# Prototype2.net
KiCad netlist of a schematic drawn in EAGLE
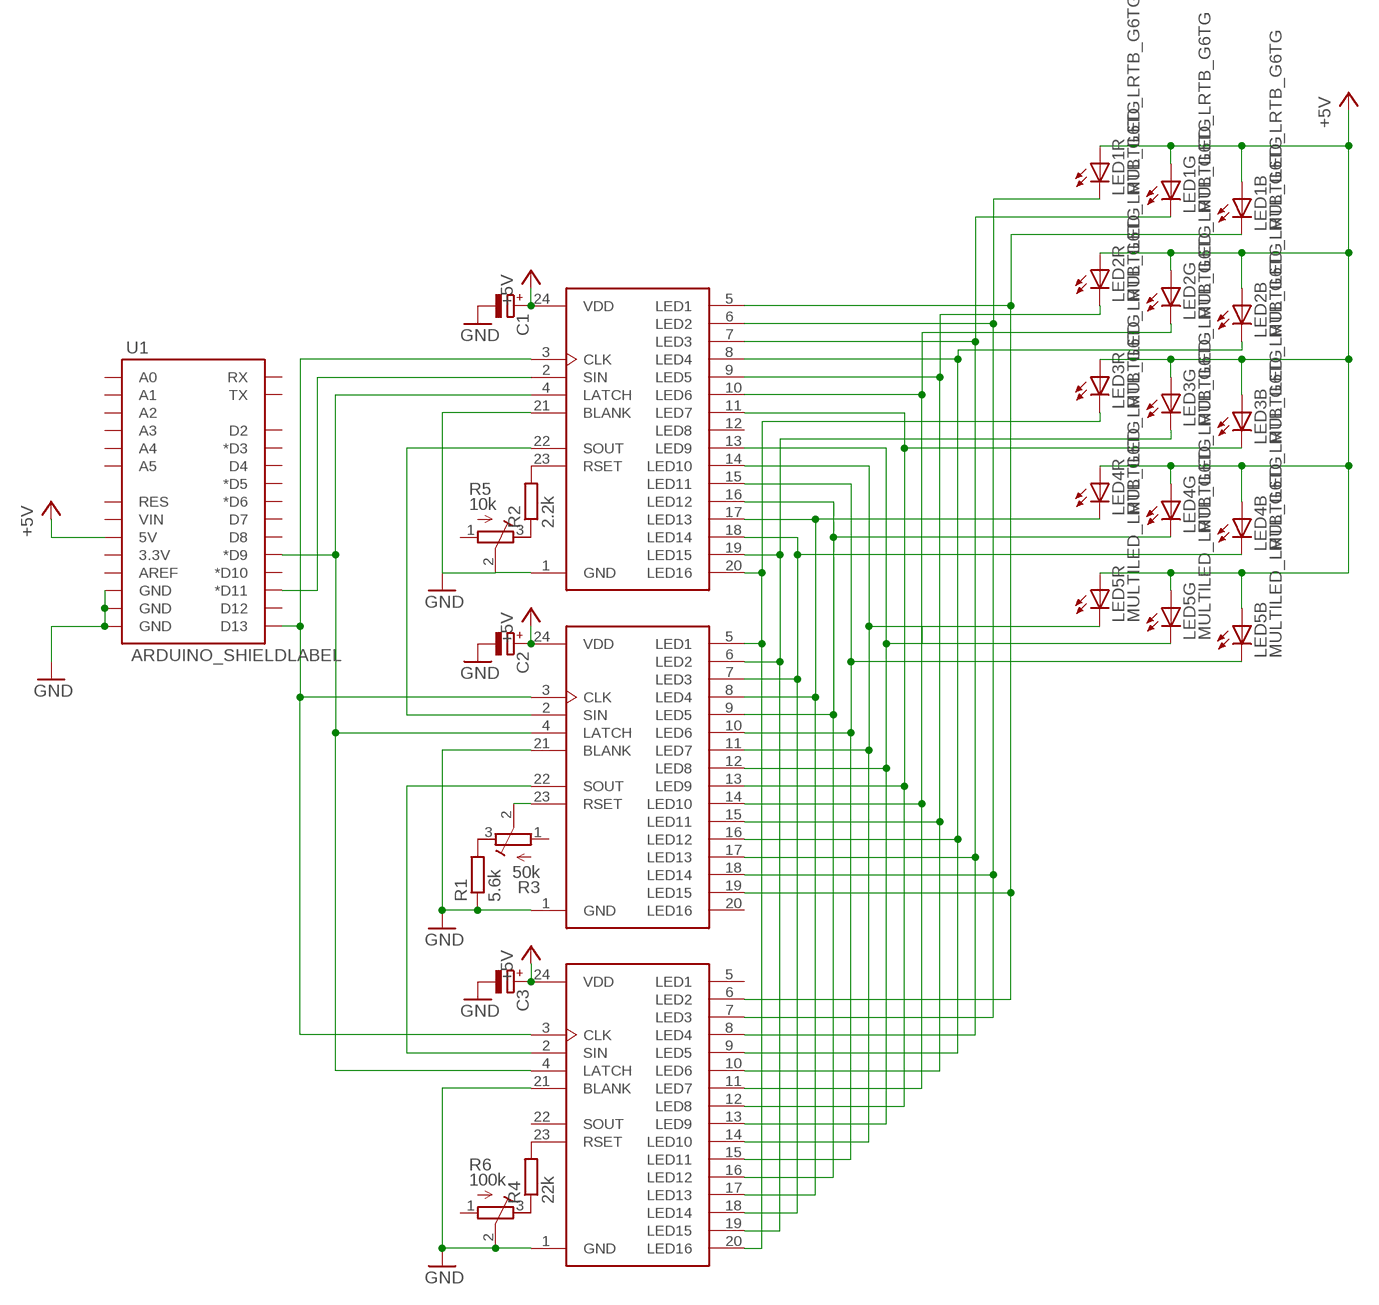
[diagram p0: schematic, sheet 1]

(export (version "E")
  (design (tool "Eeschema 10.0.6"))
  (components
    (comp (ref "C1")
      (value "CPOL-EUA/3216-18W")
      (footprint "eagle-import:A_3216-18W")
      (libsource (lib "eagle-import") (part "CPOL-EUA/3216-18W"))
    )
    (comp (ref "C2")
      (value "CPOL-EUA/3216-18W")
      (footprint "eagle-import:A_3216-18W")
      (libsource (lib "eagle-import") (part "CPOL-EUA/3216-18W"))
    )
    (comp (ref "C3")
      (value "CPOL-EUA/3216-18W")
      (footprint "eagle-import:A_3216-18W")
      (libsource (lib "eagle-import") (part "CPOL-EUA/3216-18W"))
    )
    (comp (ref "LED1")
      (value "MULTILED_LRTB_G6TG")
      (footprint "eagle-import:P-LCC-6_TOPLED")
      (libsource (lib "eagle-import") (part "MULTILED_LRTB_G6TG"))
    )
    (comp (ref "LED2")
      (value "MULTILED_LRTB_G6TG")
      (footprint "eagle-import:P-LCC-6_TOPLED")
      (libsource (lib "eagle-import") (part "MULTILED_LRTB_G6TG"))
    )
    (comp (ref "LED3")
      (value "MULTILED_LRTB_G6TG")
      (footprint "eagle-import:P-LCC-6_TOPLED")
      (libsource (lib "eagle-import") (part "MULTILED_LRTB_G6TG"))
    )
    (comp (ref "LED4")
      (value "MULTILED_LRTB_G6TG")
      (footprint "eagle-import:P-LCC-6_TOPLED")
      (libsource (lib "eagle-import") (part "MULTILED_LRTB_G6TG"))
    )
    (comp (ref "LED5")
      (value "MULTILED_LRTB_G6TG")
      (footprint "eagle-import:P-LCC-6_TOPLED")
      (libsource (lib "eagle-import") (part "MULTILED_LRTB_G6TG"))
    )
    (comp (ref "R1")
      (value "5.6k")
      (footprint "eagle-import:0204_7")
      (libsource (lib "eagle-import") (part "R-EU_0204/7"))
    )
    (comp (ref "R2")
      (value "2.2k")
      (footprint "eagle-import:0204_7")
      (libsource (lib "eagle-import") (part "R-EU_0204/7"))
    )
    (comp (ref "R3")
      (value "50k")
      (footprint "eagle-import:RTRIM3165W")
      (libsource (lib "eagle-import") (part "R-TRIMM3165W"))
    )
    (comp (ref "R4")
      (value "22k")
      (footprint "eagle-import:0204_7")
      (libsource (lib "eagle-import") (part "R-EU_0204/7"))
    )
    (comp (ref "R5")
      (value "10k")
      (footprint "eagle-import:RTRIM3165W")
      (libsource (lib "eagle-import") (part "R-TRIMM3165W"))
    )
    (comp (ref "R6")
      (value "100k")
      (footprint "eagle-import:RTRIM3165W")
      (libsource (lib "eagle-import") (part "R-TRIMM3165W"))
    )
    (comp (ref "U$1")
      (value "CAT4016")
      (footprint "eagle-import:SOIC24W")
      (libsource (lib "eagle-import") (part "CAT4016"))
    )
    (comp (ref "U$2")
      (value "CAT4016")
      (footprint "eagle-import:SOIC24W")
      (libsource (lib "eagle-import") (part "CAT4016"))
    )
    (comp (ref "U$3")
      (value "CAT4016")
      (footprint "eagle-import:SOIC24W")
      (libsource (lib "eagle-import") (part "CAT4016"))
    )
    (comp (ref "U1")
      (value "ARDUINO_SHIELDLABEL")
      (footprint "eagle-import:DUEMILANOVE_SHIELD")
      (libsource (lib "eagle-import") (part "ARDUINO_SHIELDLABEL"))
    )
  )
  (nets
    (net (code "1") (name "+5V") (class "Default")
      (node (ref "C1") (pin "+") (pinfunction "+_+") (pintype "passive"))
      (node (ref "C2") (pin "+") (pinfunction "+_+") (pintype "passive"))
      (node (ref "C3") (pin "+") (pinfunction "+_+") (pintype "passive"))
      (node (ref "LED1") (pin "A1") (pinfunction "A_A1") (pintype "passive"))
      (node (ref "LED1") (pin "A2") (pinfunction "A_A2") (pintype "passive"))
      (node (ref "LED1") (pin "A3") (pinfunction "A_A3") (pintype "passive"))
      (node (ref "LED2") (pin "A1") (pinfunction "A_A1") (pintype "passive"))
      (node (ref "LED2") (pin "A2") (pinfunction "A_A2") (pintype "passive"))
      (node (ref "LED2") (pin "A3") (pinfunction "A_A3") (pintype "passive"))
      (node (ref "LED3") (pin "A1") (pinfunction "A_A1") (pintype "passive"))
      (node (ref "LED3") (pin "A2") (pinfunction "A_A2") (pintype "passive"))
      (node (ref "LED3") (pin "A3") (pinfunction "A_A3") (pintype "passive"))
      (node (ref "LED4") (pin "A1") (pinfunction "A_A1") (pintype "passive"))
      (node (ref "LED4") (pin "A2") (pinfunction "A_A2") (pintype "passive"))
      (node (ref "LED4") (pin "A3") (pinfunction "A_A3") (pintype "passive"))
      (node (ref "LED5") (pin "A1") (pinfunction "A_A1") (pintype "passive"))
      (node (ref "LED5") (pin "A2") (pinfunction "A_A2") (pintype "passive"))
      (node (ref "LED5") (pin "A3") (pinfunction "A_A3") (pintype "passive"))
      (node (ref "U$1") (pin "24") (pinfunction "VDD_24") (pintype "bidirectional"))
      (node (ref "U$2") (pin "24") (pinfunction "VDD_24") (pintype "bidirectional"))
      (node (ref "U$3") (pin "24") (pinfunction "VDD_24") (pintype "bidirectional"))
      (node (ref "U1") (pin "5V") (pinfunction "5V_5V") (pintype "bidirectional"))
    )
    (net (code "2") (name "GND") (class "Default")
      (node (ref "C1") (pin "-") (pinfunction "-_-") (pintype "passive"))
      (node (ref "C2") (pin "-") (pinfunction "-_-") (pintype "passive"))
      (node (ref "C3") (pin "-") (pinfunction "-_-") (pintype "passive"))
      (node (ref "R1") (pin "1") (pinfunction "1_1") (pintype "passive"))
      (node (ref "R5") (pin "2") (pinfunction "S_2") (pintype "passive"))
      (node (ref "R6") (pin "2") (pinfunction "S_2") (pintype "passive"))
      (node (ref "U$1") (pin "1") (pinfunction "GND_1") (pintype "bidirectional"))
      (node (ref "U$1") (pin "21") (pinfunction "BLANK_21") (pintype "bidirectional"))
      (node (ref "U$2") (pin "1") (pinfunction "GND_1") (pintype "bidirectional"))
      (node (ref "U$2") (pin "21") (pinfunction "BLANK_21") (pintype "bidirectional"))
      (node (ref "U$3") (pin "1") (pinfunction "GND_1") (pintype "bidirectional"))
      (node (ref "U$3") (pin "21") (pinfunction "BLANK_21") (pintype "bidirectional"))
      (node (ref "U1") (pin "GND@0") (pinfunction "GND_GND@0") (pintype "bidirectional"))
      (node (ref "U1") (pin "GND@1") (pinfunction "GND_GND@1") (pintype "bidirectional"))
      (node (ref "U1") (pin "GND@2") (pinfunction "GND_GND@2") (pintype "bidirectional"))
    )
    (net (code "3") (name "Net-(LED1A-C)") (class "Default")
      (node (ref "LED1") (pin "C3") (pinfunction "C_C3") (pintype "passive"))
      (node (ref "U$1") (pin "19") (pinfunction "LED15_19") (pintype "bidirectional"))
      (node (ref "U$2") (pin "6") (pinfunction "LED2_6") (pintype "bidirectional"))
      (node (ref "U$3") (pin "5") (pinfunction "LED1_5") (pintype "bidirectional"))
    )
    (net (code "4") (name "Net-(LED1B-C)") (class "Default")
      (node (ref "LED1") (pin "C2") (pinfunction "C_C2") (pintype "passive"))
      (node (ref "U$1") (pin "17") (pinfunction "LED13_17") (pintype "bidirectional"))
      (node (ref "U$2") (pin "8") (pinfunction "LED4_8") (pintype "bidirectional"))
      (node (ref "U$3") (pin "7") (pinfunction "LED3_7") (pintype "bidirectional"))
    )
    (net (code "5") (name "Net-(LED1C-C)") (class "Default")
      (node (ref "LED1") (pin "C1") (pinfunction "C_C1") (pintype "passive"))
      (node (ref "U$1") (pin "18") (pinfunction "LED14_18") (pintype "bidirectional"))
      (node (ref "U$2") (pin "7") (pinfunction "LED3_7") (pintype "bidirectional"))
      (node (ref "U$3") (pin "6") (pinfunction "LED2_6") (pintype "bidirectional"))
    )
    (net (code "6") (name "Net-(LED2A-C)") (class "Default")
      (node (ref "LED2") (pin "C3") (pinfunction "C_C3") (pintype "passive"))
      (node (ref "U$1") (pin "16") (pinfunction "LED12_16") (pintype "bidirectional"))
      (node (ref "U$2") (pin "9") (pinfunction "LED5_9") (pintype "bidirectional"))
      (node (ref "U$3") (pin "8") (pinfunction "LED4_8") (pintype "bidirectional"))
    )
    (net (code "7") (name "Net-(LED2B-C)") (class "Default")
      (node (ref "LED2") (pin "C2") (pinfunction "C_C2") (pintype "passive"))
      (node (ref "U$1") (pin "14") (pinfunction "LED10_14") (pintype "bidirectional"))
      (node (ref "U$2") (pin "11") (pinfunction "LED7_11") (pintype "bidirectional"))
      (node (ref "U$3") (pin "10") (pinfunction "LED6_10") (pintype "bidirectional"))
    )
    (net (code "8") (name "Net-(LED2C-C)") (class "Default")
      (node (ref "LED2") (pin "C1") (pinfunction "C_C1") (pintype "passive"))
      (node (ref "U$1") (pin "15") (pinfunction "LED11_15") (pintype "bidirectional"))
      (node (ref "U$2") (pin "10") (pinfunction "LED6_10") (pintype "bidirectional"))
      (node (ref "U$3") (pin "9") (pinfunction "LED5_9") (pintype "bidirectional"))
    )
    (net (code "9") (name "Net-(LED3A-C)") (class "Default")
      (node (ref "LED3") (pin "C3") (pinfunction "C_C3") (pintype "passive"))
      (node (ref "U$1") (pin "13") (pinfunction "LED9_13") (pintype "bidirectional"))
      (node (ref "U$2") (pin "12") (pinfunction "LED8_12") (pintype "bidirectional"))
      (node (ref "U$3") (pin "11") (pinfunction "LED7_11") (pintype "bidirectional"))
    )
    (net (code "10") (name "Net-(LED3B-C)") (class "Default")
      (node (ref "LED3") (pin "C2") (pinfunction "C_C2") (pintype "passive"))
      (node (ref "U$1") (pin "6") (pinfunction "LED2_6") (pintype "bidirectional"))
      (node (ref "U$2") (pin "19") (pinfunction "LED15_19") (pintype "bidirectional"))
      (node (ref "U$3") (pin "19") (pinfunction "LED15_19") (pintype "bidirectional"))
    )
    (net (code "11") (name "Net-(LED3C-C)") (class "Default")
      (node (ref "LED3") (pin "C1") (pinfunction "C_C1") (pintype "passive"))
      (node (ref "U$1") (pin "5") (pinfunction "LED1_5") (pintype "bidirectional"))
      (node (ref "U$2") (pin "20") (pinfunction "LED16_20") (pintype "bidirectional"))
      (node (ref "U$3") (pin "20") (pinfunction "LED16_20") (pintype "bidirectional"))
    )
    (net (code "12") (name "Net-(LED4A-C)") (class "Default")
      (node (ref "LED4") (pin "C3") (pinfunction "C_C3") (pintype "passive"))
      (node (ref "U$1") (pin "7") (pinfunction "LED3_7") (pintype "bidirectional"))
      (node (ref "U$2") (pin "18") (pinfunction "LED14_18") (pintype "bidirectional"))
      (node (ref "U$3") (pin "18") (pinfunction "LED14_18") (pintype "bidirectional"))
    )
    (net (code "13") (name "Net-(LED4B-C)") (class "Default")
      (node (ref "LED4") (pin "C2") (pinfunction "C_C2") (pintype "passive"))
      (node (ref "U$1") (pin "9") (pinfunction "LED5_9") (pintype "bidirectional"))
      (node (ref "U$2") (pin "16") (pinfunction "LED12_16") (pintype "bidirectional"))
      (node (ref "U$3") (pin "16") (pinfunction "LED12_16") (pintype "bidirectional"))
    )
    (net (code "14") (name "Net-(LED4C-C)") (class "Default")
      (node (ref "LED4") (pin "C1") (pinfunction "C_C1") (pintype "passive"))
      (node (ref "U$1") (pin "8") (pinfunction "LED4_8") (pintype "bidirectional"))
      (node (ref "U$2") (pin "17") (pinfunction "LED13_17") (pintype "bidirectional"))
      (node (ref "U$3") (pin "17") (pinfunction "LED13_17") (pintype "bidirectional"))
    )
    (net (code "15") (name "Net-(LED5A-C)") (class "Default")
      (node (ref "LED5") (pin "C3") (pinfunction "C_C3") (pintype "passive"))
      (node (ref "U$1") (pin "10") (pinfunction "LED6_10") (pintype "bidirectional"))
      (node (ref "U$2") (pin "15") (pinfunction "LED11_15") (pintype "bidirectional"))
      (node (ref "U$3") (pin "15") (pinfunction "LED11_15") (pintype "bidirectional"))
    )
    (net (code "16") (name "Net-(LED5B-C)") (class "Default")
      (node (ref "LED5") (pin "C2") (pinfunction "C_C2") (pintype "passive"))
      (node (ref "U$1") (pin "12") (pinfunction "LED8_12") (pintype "bidirectional"))
      (node (ref "U$2") (pin "13") (pinfunction "LED9_13") (pintype "bidirectional"))
      (node (ref "U$3") (pin "13") (pinfunction "LED9_13") (pintype "bidirectional"))
    )
    (net (code "17") (name "Net-(LED5C-C)") (class "Default")
      (node (ref "LED5") (pin "C1") (pinfunction "C_C1") (pintype "passive"))
      (node (ref "U$1") (pin "11") (pinfunction "LED7_11") (pintype "bidirectional"))
      (node (ref "U$2") (pin "14") (pinfunction "LED10_14") (pintype "bidirectional"))
      (node (ref "U$3") (pin "14") (pinfunction "LED10_14") (pintype "bidirectional"))
    )
    (net (code "18") (name "Net-(R3-E)") (class "Default")
      (node (ref "R1") (pin "2") (pinfunction "2_2") (pintype "passive"))
      (node (ref "R3") (pin "3") (pinfunction "E_3") (pintype "passive"))
    )
    (net (code "19") (name "Net-(R3-S)") (class "Default")
      (node (ref "R3") (pin "2") (pinfunction "S_2") (pintype "passive"))
      (node (ref "U$1") (pin "23") (pinfunction "RSET_23") (pintype "bidirectional"))
    )
    (net (code "20") (name "Net-(R5-E)") (class "Default")
      (node (ref "R2") (pin "1") (pinfunction "1_1") (pintype "passive"))
      (node (ref "R5") (pin "3") (pinfunction "E_3") (pintype "passive"))
    )
    (net (code "21") (name "Net-(R6-E)") (class "Default")
      (node (ref "R4") (pin "1") (pinfunction "1_1") (pintype "passive"))
      (node (ref "R6") (pin "3") (pinfunction "E_3") (pintype "passive"))
    )
    (net (code "22") (name "Net-(U$1-CLK)") (class "Default")
      (node (ref "U$1") (pin "3") (pinfunction "CLK_3") (pintype "bidirectional"))
      (node (ref "U$2") (pin "3") (pinfunction "CLK_3") (pintype "bidirectional"))
      (node (ref "U$3") (pin "3") (pinfunction "CLK_3") (pintype "bidirectional"))
      (node (ref "U1") (pin "D13") (pinfunction "D13_D13") (pintype "bidirectional"))
    )
    (net (code "23") (name "Net-(U$1-LATCH)") (class "Default")
      (node (ref "U$1") (pin "4") (pinfunction "LATCH_4") (pintype "bidirectional"))
      (node (ref "U$2") (pin "4") (pinfunction "LATCH_4") (pintype "bidirectional"))
      (node (ref "U$3") (pin "4") (pinfunction "LATCH_4") (pintype "bidirectional"))
      (node (ref "U1") (pin "D9") (pinfunction "*D9_D9") (pintype "bidirectional"))
    )
    (net (code "24") (name "Net-(U$1-SIN)") (class "Default")
      (node (ref "U$1") (pin "2") (pinfunction "SIN_2") (pintype "bidirectional"))
      (node (ref "U$3") (pin "22") (pinfunction "SOUT_22") (pintype "bidirectional"))
    )
    (net (code "25") (name "Net-(U$1-SOUT)") (class "Default")
      (node (ref "U$1") (pin "22") (pinfunction "SOUT_22") (pintype "bidirectional"))
      (node (ref "U$2") (pin "2") (pinfunction "SIN_2") (pintype "bidirectional"))
    )
    (net (code "26") (name "Net-(U$2-RSET)") (class "Default")
      (node (ref "R4") (pin "2") (pinfunction "2_2") (pintype "passive"))
      (node (ref "U$2") (pin "23") (pinfunction "RSET_23") (pintype "bidirectional"))
    )
    (net (code "27") (name "Net-(U$3-RSET)") (class "Default")
      (node (ref "R2") (pin "2") (pinfunction "2_2") (pintype "passive"))
      (node (ref "U$3") (pin "23") (pinfunction "RSET_23") (pintype "bidirectional"))
    )
    (net (code "28") (name "Net-(U$3-SIN)") (class "Default")
      (node (ref "U$3") (pin "2") (pinfunction "SIN_2") (pintype "bidirectional"))
      (node (ref "U1") (pin "D11") (pinfunction "*D11_D11") (pintype "bidirectional"))
    )
    (net (code "29") (name "unconnected-(R3-A-Pad1)") (class "Default")
      (node (ref "R3") (pin "1") (pinfunction "A_1") (pintype "passive"))
    )
    (net (code "30") (name "unconnected-(R5-A-Pad1)") (class "Default")
      (node (ref "R5") (pin "1") (pinfunction "A_1") (pintype "passive"))
    )
    (net (code "31") (name "unconnected-(R6-A-Pad1)") (class "Default")
      (node (ref "R6") (pin "1") (pinfunction "A_1") (pintype "passive"))
    )
    (net (code "32") (name "unconnected-(U$1-LED16-Pad20)") (class "Default")
      (node (ref "U$1") (pin "20") (pinfunction "LED16_20") (pintype "bidirectional"))
    )
    (net (code "33") (name "unconnected-(U$2-LED1-Pad5)") (class "Default")
      (node (ref "U$2") (pin "5") (pinfunction "LED1_5") (pintype "bidirectional"))
    )
    (net (code "34") (name "unconnected-(U$2-SOUT-Pad22)") (class "Default")
      (node (ref "U$2") (pin "22") (pinfunction "SOUT_22") (pintype "bidirectional"))
    )
    (net (code "35") (name "unconnected-(U$3-LED8-Pad12)") (class "Default")
      (node (ref "U$3") (pin "12") (pinfunction "LED8_12") (pintype "bidirectional"))
    )
    (net (code "36") (name "unconnected-(U1-*D3-PadD3)") (class "Default")
      (node (ref "U1") (pin "D3") (pinfunction "*D3_D3") (pintype "bidirectional"))
    )
    (net (code "37") (name "unconnected-(U1-*D5-PadD5)") (class "Default")
      (node (ref "U1") (pin "D5") (pinfunction "*D5_D5") (pintype "bidirectional"))
    )
    (net (code "38") (name "unconnected-(U1-*D6-PadD6)") (class "Default")
      (node (ref "U1") (pin "D6") (pinfunction "*D6_D6") (pintype "bidirectional"))
    )
    (net (code "39") (name "unconnected-(U1-*D10-PadD10)") (class "Default")
      (node (ref "U1") (pin "D10") (pinfunction "*D10_D10") (pintype "bidirectional"))
    )
    (net (code "40") (name "unconnected-(U1-Pad3.3V)") (class "Default")
      (node (ref "U1") (pin "3.3V") (pinfunction "3.3V_3.3V") (pintype "bidirectional"))
    )
    (net (code "41") (name "unconnected-(U1-PadA0)") (class "Default")
      (node (ref "U1") (pin "A0") (pinfunction "A0_A0") (pintype "bidirectional"))
    )
    (net (code "42") (name "unconnected-(U1-PadA1)") (class "Default")
      (node (ref "U1") (pin "A1") (pinfunction "A1_A1") (pintype "bidirectional"))
    )
    (net (code "43") (name "unconnected-(U1-PadA2)") (class "Default")
      (node (ref "U1") (pin "A2") (pinfunction "A2_A2") (pintype "bidirectional"))
    )
    (net (code "44") (name "unconnected-(U1-PadA3)") (class "Default")
      (node (ref "U1") (pin "A3") (pinfunction "A3_A3") (pintype "bidirectional"))
    )
    (net (code "45") (name "unconnected-(U1-PadA4)") (class "Default")
      (node (ref "U1") (pin "A4") (pinfunction "A4_A4") (pintype "bidirectional"))
    )
    (net (code "46") (name "unconnected-(U1-PadA5)") (class "Default")
      (node (ref "U1") (pin "A5") (pinfunction "A5_A5") (pintype "bidirectional"))
    )
    (net (code "47") (name "unconnected-(U1-PadAREF)") (class "Default")
      (node (ref "U1") (pin "AREF") (pinfunction "AREF_AREF") (pintype "bidirectional"))
    )
    (net (code "48") (name "unconnected-(U1-PadD2)") (class "Default")
      (node (ref "U1") (pin "D2") (pinfunction "D2_D2") (pintype "bidirectional"))
    )
    (net (code "49") (name "unconnected-(U1-PadD4)") (class "Default")
      (node (ref "U1") (pin "D4") (pinfunction "D4_D4") (pintype "bidirectional"))
    )
    (net (code "50") (name "unconnected-(U1-PadD7)") (class "Default")
      (node (ref "U1") (pin "D7") (pinfunction "D7_D7") (pintype "bidirectional"))
    )
    (net (code "51") (name "unconnected-(U1-PadD8)") (class "Default")
      (node (ref "U1") (pin "D8") (pinfunction "D8_D8") (pintype "bidirectional"))
    )
    (net (code "52") (name "unconnected-(U1-PadD12)") (class "Default")
      (node (ref "U1") (pin "D12") (pinfunction "D12_D12") (pintype "bidirectional"))
    )
    (net (code "53") (name "unconnected-(U1-PadRES)") (class "Default")
      (node (ref "U1") (pin "RES") (pinfunction "RES_RES") (pintype "bidirectional"))
    )
    (net (code "54") (name "unconnected-(U1-PadRX)") (class "Default")
      (node (ref "U1") (pin "RX") (pinfunction "RX_RX") (pintype "bidirectional"))
    )
    (net (code "55") (name "unconnected-(U1-PadTX)") (class "Default")
      (node (ref "U1") (pin "TX") (pinfunction "TX_TX") (pintype "bidirectional"))
    )
    (net (code "56") (name "unconnected-(U1-PadVIN)") (class "Default")
      (node (ref "U1") (pin "VIN") (pinfunction "VIN_VIN") (pintype "bidirectional"))
    )
  )
)
